# 7953_VHDC.net
KiCad netlist of a schematic drawn in Altium Designer
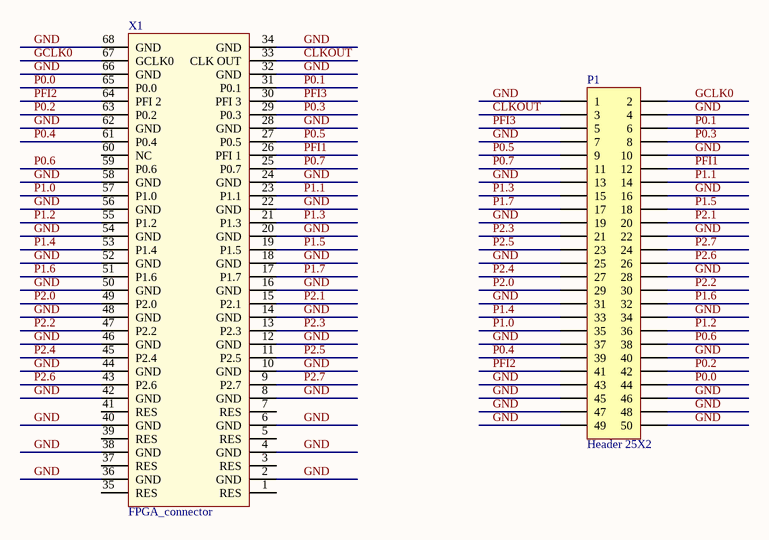
[diagram p0: 7953_VHDC.SchDoc]

(export (version "E")
  (design (tool "Eeschema 10.0.6"))
  (components
    (comp (ref "P1")
      (value "Header 25X2")
      (footprint "HDR2X25")
      (description "Header, 25-Pin, Dual row")
      (fields (field (name "PUBLISHER") "Altium Limited"))
      (libsource (lib "Miscellaneous Connectors") (part "Header 25X2"))
    )
    (comp (ref "X1")
      (value "FPGA_connector")
      (footprint "FPGA")
      (libsource (lib "Schlib") (part "FPGA_Connector"))
    )
  )
  (nets
    (net (code "1") (name "/CLKOUT") (class "Default")
      (node (ref "P1") (pin "3") (pinfunction "3_3") (pintype "passive"))
      (node (ref "X1") (pin "33") (pinfunction "CLK_OUT_33") (pintype "passive"))
    )
    (net (code "2") (name "/GCLK0") (class "Default")
      (node (ref "P1") (pin "2") (pinfunction "2_2") (pintype "passive"))
      (node (ref "X1") (pin "67") (pinfunction "GCLK0_67") (pintype "passive"))
    )
    (net (code "3") (name "/GND") (class "Default")
      (node (ref "P1") (pin "1") (pinfunction "1_1") (pintype "passive"))
      (node (ref "P1") (pin "10") (pinfunction "10_10") (pintype "passive"))
      (node (ref "P1") (pin "13") (pinfunction "13_13") (pintype "passive"))
      (node (ref "P1") (pin "16") (pinfunction "16_16") (pintype "passive"))
      (node (ref "P1") (pin "19") (pinfunction "19_19") (pintype "passive"))
      (node (ref "P1") (pin "22") (pinfunction "22_22") (pintype "passive"))
      (node (ref "P1") (pin "25") (pinfunction "25_25") (pintype "passive"))
      (node (ref "P1") (pin "28") (pinfunction "28_28") (pintype "passive"))
      (node (ref "P1") (pin "31") (pinfunction "31_31") (pintype "passive"))
      (node (ref "P1") (pin "34") (pinfunction "34_34") (pintype "passive"))
      (node (ref "P1") (pin "37") (pinfunction "37_37") (pintype "passive"))
      (node (ref "P1") (pin "4") (pinfunction "4_4") (pintype "passive"))
      (node (ref "P1") (pin "40") (pinfunction "40_40") (pintype "passive"))
      (node (ref "P1") (pin "43") (pinfunction "43_43") (pintype "passive"))
      (node (ref "P1") (pin "45") (pinfunction "45_45") (pintype "passive"))
      (node (ref "P1") (pin "46") (pinfunction "46_46") (pintype "passive"))
      (node (ref "P1") (pin "47") (pinfunction "47_47") (pintype "passive"))
      (node (ref "P1") (pin "48") (pinfunction "48_48") (pintype "passive"))
      (node (ref "P1") (pin "49") (pinfunction "49_49") (pintype "passive"))
      (node (ref "P1") (pin "50") (pinfunction "50_50") (pintype "passive"))
      (node (ref "P1") (pin "7") (pinfunction "7_7") (pintype "passive"))
      (node (ref "X1") (pin "10") (pinfunction "GND_10") (pintype "passive"))
      (node (ref "X1") (pin "12") (pinfunction "GND_12") (pintype "passive"))
      (node (ref "X1") (pin "14") (pinfunction "GND_14") (pintype "passive"))
      (node (ref "X1") (pin "16") (pinfunction "GND_16") (pintype "passive"))
      (node (ref "X1") (pin "18") (pinfunction "GND_18") (pintype "passive"))
      (node (ref "X1") (pin "2") (pinfunction "GND_2") (pintype "passive"))
      (node (ref "X1") (pin "20") (pinfunction "GND_20") (pintype "passive"))
      (node (ref "X1") (pin "22") (pinfunction "GND_22") (pintype "passive"))
      (node (ref "X1") (pin "24") (pinfunction "GND_24") (pintype "passive"))
      (node (ref "X1") (pin "28") (pinfunction "GND_28") (pintype "passive"))
      (node (ref "X1") (pin "32") (pinfunction "GND_32") (pintype "passive"))
      (node (ref "X1") (pin "34") (pinfunction "GND_34") (pintype "passive"))
      (node (ref "X1") (pin "36") (pinfunction "GND_36") (pintype "passive"))
      (node (ref "X1") (pin "38") (pinfunction "GND_38") (pintype "passive"))
      (node (ref "X1") (pin "4") (pinfunction "GND_4") (pintype "passive"))
      (node (ref "X1") (pin "40") (pinfunction "GND_40") (pintype "passive"))
      (node (ref "X1") (pin "42") (pinfunction "GND_42") (pintype "passive"))
      (node (ref "X1") (pin "44") (pinfunction "GND_44") (pintype "passive"))
      (node (ref "X1") (pin "46") (pinfunction "GND_46") (pintype "passive"))
      (node (ref "X1") (pin "48") (pinfunction "GND_48") (pintype "passive"))
      (node (ref "X1") (pin "50") (pinfunction "GND_50") (pintype "passive"))
      (node (ref "X1") (pin "52") (pinfunction "GND_52") (pintype "passive"))
      (node (ref "X1") (pin "54") (pinfunction "GND_54") (pintype "passive"))
      (node (ref "X1") (pin "56") (pinfunction "GND_56") (pintype "passive"))
      (node (ref "X1") (pin "58") (pinfunction "GND_58") (pintype "passive"))
      (node (ref "X1") (pin "6") (pinfunction "GND_6") (pintype "passive"))
      (node (ref "X1") (pin "62") (pinfunction "GND_62") (pintype "passive"))
      (node (ref "X1") (pin "66") (pinfunction "GND_66") (pintype "passive"))
      (node (ref "X1") (pin "68") (pinfunction "GND_68") (pintype "passive"))
      (node (ref "X1") (pin "8") (pinfunction "GND_8") (pintype "passive"))
    )
    (net (code "4") (name "/P0.0") (class "Default")
      (node (ref "P1") (pin "44") (pinfunction "44_44") (pintype "passive"))
      (node (ref "X1") (pin "65") (pinfunction "P0.0_65") (pintype "passive"))
    )
    (net (code "5") (name "/P0.1") (class "Default")
      (node (ref "P1") (pin "6") (pinfunction "6_6") (pintype "passive"))
      (node (ref "X1") (pin "31") (pinfunction "P0.1_31") (pintype "passive"))
    )
    (net (code "6") (name "/P0.2") (class "Default")
      (node (ref "P1") (pin "42") (pinfunction "42_42") (pintype "passive"))
      (node (ref "X1") (pin "63") (pinfunction "P0.2_63") (pintype "passive"))
    )
    (net (code "7") (name "/P0.3") (class "Default")
      (node (ref "P1") (pin "8") (pinfunction "8_8") (pintype "passive"))
      (node (ref "X1") (pin "29") (pinfunction "P0.3_29") (pintype "passive"))
    )
    (net (code "8") (name "/P0.4") (class "Default")
      (node (ref "P1") (pin "39") (pinfunction "39_39") (pintype "passive"))
      (node (ref "X1") (pin "61") (pinfunction "P0.4_61") (pintype "passive"))
    )
    (net (code "9") (name "/P0.5") (class "Default")
      (node (ref "P1") (pin "9") (pinfunction "9_9") (pintype "passive"))
      (node (ref "X1") (pin "27") (pinfunction "P0.5_27") (pintype "passive"))
    )
    (net (code "10") (name "/P0.6") (class "Default")
      (node (ref "P1") (pin "38") (pinfunction "38_38") (pintype "passive"))
      (node (ref "X1") (pin "59") (pinfunction "P0.6_59") (pintype "passive"))
    )
    (net (code "11") (name "/P0.7") (class "Default")
      (node (ref "P1") (pin "11") (pinfunction "11_11") (pintype "passive"))
      (node (ref "X1") (pin "25") (pinfunction "P0.7_25") (pintype "passive"))
    )
    (net (code "12") (name "/P1.0") (class "Default")
      (node (ref "P1") (pin "35") (pinfunction "35_35") (pintype "passive"))
      (node (ref "X1") (pin "57") (pinfunction "P1.0_57") (pintype "passive"))
    )
    (net (code "13") (name "/P1.1") (class "Default")
      (node (ref "P1") (pin "14") (pinfunction "14_14") (pintype "passive"))
      (node (ref "X1") (pin "23") (pinfunction "P1.1_23") (pintype "passive"))
    )
    (net (code "14") (name "/P1.2") (class "Default")
      (node (ref "P1") (pin "36") (pinfunction "36_36") (pintype "passive"))
      (node (ref "X1") (pin "55") (pinfunction "P1.2_55") (pintype "passive"))
    )
    (net (code "15") (name "/P1.3") (class "Default")
      (node (ref "P1") (pin "15") (pinfunction "15_15") (pintype "passive"))
      (node (ref "X1") (pin "21") (pinfunction "P1.3_21") (pintype "passive"))
    )
    (net (code "16") (name "/P1.4") (class "Default")
      (node (ref "P1") (pin "33") (pinfunction "33_33") (pintype "passive"))
      (node (ref "X1") (pin "53") (pinfunction "P1.4_53") (pintype "passive"))
    )
    (net (code "17") (name "/P1.5") (class "Default")
      (node (ref "P1") (pin "18") (pinfunction "18_18") (pintype "passive"))
      (node (ref "X1") (pin "19") (pinfunction "P1.5_19") (pintype "passive"))
    )
    (net (code "18") (name "/P1.6") (class "Default")
      (node (ref "P1") (pin "32") (pinfunction "32_32") (pintype "passive"))
      (node (ref "X1") (pin "51") (pinfunction "P1.6_51") (pintype "passive"))
    )
    (net (code "19") (name "/P1.7") (class "Default")
      (node (ref "P1") (pin "17") (pinfunction "17_17") (pintype "passive"))
      (node (ref "X1") (pin "17") (pinfunction "P1.7_17") (pintype "passive"))
    )
    (net (code "20") (name "/P2.0") (class "Default")
      (node (ref "P1") (pin "29") (pinfunction "29_29") (pintype "passive"))
      (node (ref "X1") (pin "49") (pinfunction "P2.0_49") (pintype "passive"))
    )
    (net (code "21") (name "/P2.1") (class "Default")
      (node (ref "P1") (pin "20") (pinfunction "20_20") (pintype "passive"))
      (node (ref "X1") (pin "15") (pinfunction "P2.1_15") (pintype "passive"))
    )
    (net (code "22") (name "/P2.2") (class "Default")
      (node (ref "P1") (pin "30") (pinfunction "30_30") (pintype "passive"))
      (node (ref "X1") (pin "47") (pinfunction "P2.2_47") (pintype "passive"))
    )
    (net (code "23") (name "/P2.3") (class "Default")
      (node (ref "P1") (pin "21") (pinfunction "21_21") (pintype "passive"))
      (node (ref "X1") (pin "13") (pinfunction "P2.3_13") (pintype "passive"))
    )
    (net (code "24") (name "/P2.4") (class "Default")
      (node (ref "P1") (pin "27") (pinfunction "27_27") (pintype "passive"))
      (node (ref "X1") (pin "45") (pinfunction "P2.4_45") (pintype "passive"))
    )
    (net (code "25") (name "/P2.5") (class "Default")
      (node (ref "P1") (pin "23") (pinfunction "23_23") (pintype "passive"))
      (node (ref "X1") (pin "11") (pinfunction "P2.5_11") (pintype "passive"))
    )
    (net (code "26") (name "/P2.6") (class "Default")
      (node (ref "P1") (pin "26") (pinfunction "26_26") (pintype "passive"))
      (node (ref "X1") (pin "43") (pinfunction "P2.6_43") (pintype "passive"))
    )
    (net (code "27") (name "/P2.7") (class "Default")
      (node (ref "P1") (pin "24") (pinfunction "24_24") (pintype "passive"))
      (node (ref "X1") (pin "9") (pinfunction "P2.7_9") (pintype "passive"))
    )
    (net (code "28") (name "/PFI1") (class "Default")
      (node (ref "P1") (pin "12") (pinfunction "12_12") (pintype "passive"))
      (node (ref "X1") (pin "26") (pinfunction "PFI_1_26") (pintype "passive"))
    )
    (net (code "29") (name "/PFI2") (class "Default")
      (node (ref "P1") (pin "41") (pinfunction "41_41") (pintype "passive"))
      (node (ref "X1") (pin "64") (pinfunction "PFI_2_64") (pintype "passive"))
    )
    (net (code "30") (name "/PFI3") (class "Default")
      (node (ref "P1") (pin "5") (pinfunction "5_5") (pintype "passive"))
      (node (ref "X1") (pin "30") (pinfunction "PFI_3_30") (pintype "passive"))
    )
    (net (code "31") (name "unconnected-(X1-NC-Pad60)") (class "Default")
      (node (ref "X1") (pin "60") (pinfunction "NC_60") (pintype "passive"))
    )
    (net (code "32") (name "unconnected-(X1-RES-Pad1)") (class "Default")
      (node (ref "X1") (pin "1") (pinfunction "RES_1") (pintype "passive"))
    )
    (net (code "33") (name "unconnected-(X1-RES-Pad3)") (class "Default")
      (node (ref "X1") (pin "3") (pinfunction "RES_3") (pintype "passive"))
    )
    (net (code "34") (name "unconnected-(X1-RES-Pad5)") (class "Default")
      (node (ref "X1") (pin "5") (pinfunction "RES_5") (pintype "passive"))
    )
    (net (code "35") (name "unconnected-(X1-RES-Pad7)") (class "Default")
      (node (ref "X1") (pin "7") (pinfunction "RES_7") (pintype "passive"))
    )
    (net (code "36") (name "unconnected-(X1-RES-Pad35)") (class "Default")
      (node (ref "X1") (pin "35") (pinfunction "RES_35") (pintype "passive"))
    )
    (net (code "37") (name "unconnected-(X1-RES-Pad37)") (class "Default")
      (node (ref "X1") (pin "37") (pinfunction "RES_37") (pintype "passive"))
    )
    (net (code "38") (name "unconnected-(X1-RES-Pad39)") (class "Default")
      (node (ref "X1") (pin "39") (pinfunction "RES_39") (pintype "passive"))
    )
    (net (code "39") (name "unconnected-(X1-RES-Pad41)") (class "Default")
      (node (ref "X1") (pin "41") (pinfunction "RES_41") (pintype "passive"))
    )
  )
)
